# Netzteil_Darlington_v2_Frontpanel.net
KiCad netlist of a schematic drawn in EAGLE
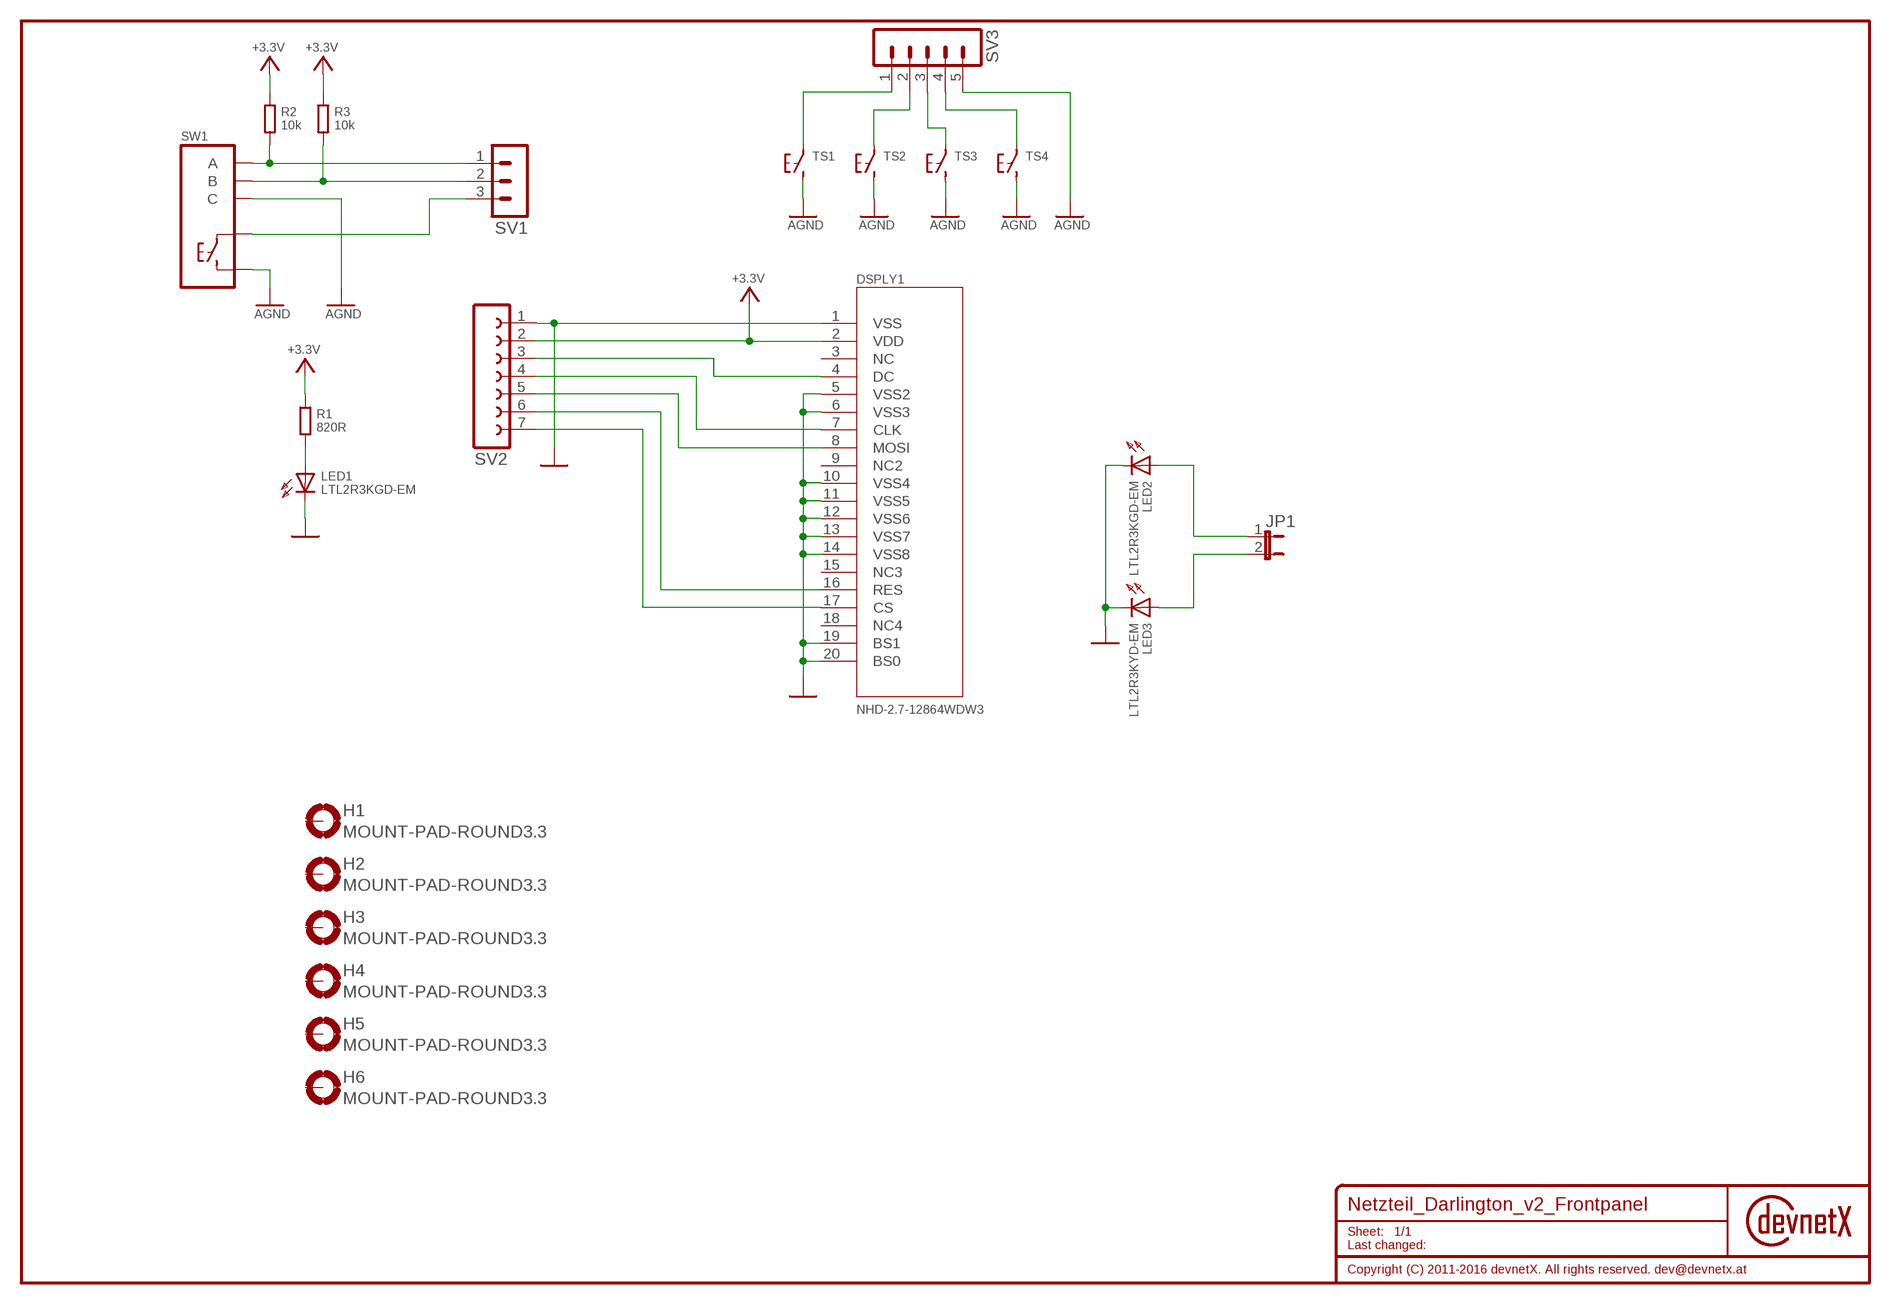
[diagram p0: schematic, sheet 1]

(export (version "E")
  (design (tool "Eeschema 10.0.6"))
  (components
    (comp (ref "DNX-NAME-1")
      (value "DOC-R1.27")
      (footprint "eagle-import:DRAWINGNAME-1.27")
      (libsource (lib "eagle-import") (part "DOC-R1.27"))
    )
    (comp (ref "DSPLY1")
      (value "NHD-2.7-12864WDW3")
      (footprint "eagle-import:NHD-2.7-12864WDW3")
      (libsource (lib "eagle-import") (part "NHD-2.7-12864WDW3"))
    )
    (comp (ref "H1")
      (value "MOUNT-PAD-ROUND3.3")
      (footprint "eagle-import:3,3-PAD")
      (libsource (lib "eagle-import") (part "MOUNT-PAD-ROUND3.3"))
    )
    (comp (ref "H2")
      (value "MOUNT-PAD-ROUND3.3")
      (footprint "eagle-import:3,3-PAD")
      (libsource (lib "eagle-import") (part "MOUNT-PAD-ROUND3.3"))
    )
    (comp (ref "H3")
      (value "MOUNT-PAD-ROUND3.3")
      (footprint "eagle-import:3,3-PAD")
      (libsource (lib "eagle-import") (part "MOUNT-PAD-ROUND3.3"))
    )
    (comp (ref "H4")
      (value "MOUNT-PAD-ROUND3.3")
      (footprint "eagle-import:3,3-PAD")
      (libsource (lib "eagle-import") (part "MOUNT-PAD-ROUND3.3"))
    )
    (comp (ref "H5")
      (value "MOUNT-PAD-ROUND3.3")
      (footprint "eagle-import:3,3-PAD")
      (libsource (lib "eagle-import") (part "MOUNT-PAD-ROUND3.3"))
    )
    (comp (ref "H6")
      (value "MOUNT-PAD-ROUND3.3")
      (footprint "eagle-import:3,3-PAD")
      (libsource (lib "eagle-import") (part "MOUNT-PAD-ROUND3.3"))
    )
    (comp (ref "JP1")
      (value "JP1E")
      (footprint "eagle-import:JP1")
      (libsource (lib "eagle-import") (part "JP1E"))
    )
    (comp (ref "LED1")
      (value "LTL2R3KGD-EM")
      (footprint "eagle-import:LED5MM")
      (libsource (lib "eagle-import") (part "LEDLED5MM"))
    )
    (comp (ref "LED2")
      (value "LTL2R3KGD-EM")
      (footprint "eagle-import:LED5MM")
      (libsource (lib "eagle-import") (part "LEDLED5MM"))
    )
    (comp (ref "LED3")
      (value "LTL2R3KYD-EM")
      (footprint "eagle-import:LED5MM")
      (libsource (lib "eagle-import") (part "LEDLED5MM"))
    )
    (comp (ref "R1")
      (value "820R")
      (footprint "eagle-import:C0805K")
      (libsource (lib "eagle-import") (part "R-SMD0805"))
    )
    (comp (ref "R2")
      (value "10k")
      (footprint "eagle-import:C0805K")
      (libsource (lib "eagle-import") (part "R-SMD0805"))
    )
    (comp (ref "R3")
      (value "10k")
      (footprint "eagle-import:C0805K")
      (libsource (lib "eagle-import") (part "R-SMD0805"))
    )
    (comp (ref "SV1")
      (value "MA03-1")
      (footprint "eagle-import:MA03-1")
      (libsource (lib "eagle-import") (part "MA03-1"))
    )
    (comp (ref "SV2")
      (value "FE07-1")
      (footprint "eagle-import:FE07")
      (libsource (lib "eagle-import") (part "FE07-1"))
    )
    (comp (ref "SV3")
      (value "MA05-1")
      (footprint "eagle-import:MA05-1")
      (libsource (lib "eagle-import") (part "MA05-1"))
    )
    (comp (ref "SW1")
      (value "EC12E-SW")
      (footprint "eagle-import:EC12E-SW")
      (libsource (lib "eagle-import") (part "EC12E-SW"))
    )
    (comp (ref "TS1")
      (value "TS1B3F-10XX")
      (footprint "eagle-import:B3F-10XX")
      (libsource (lib "eagle-import") (part "TS1B3F-10XX"))
    )
    (comp (ref "TS2")
      (value "TS1B3F-10XX")
      (footprint "eagle-import:B3F-10XX")
      (libsource (lib "eagle-import") (part "TS1B3F-10XX"))
    )
    (comp (ref "TS3")
      (value "TS1B3F-10XX")
      (footprint "eagle-import:B3F-10XX")
      (libsource (lib "eagle-import") (part "TS1B3F-10XX"))
    )
    (comp (ref "TS4")
      (value "TS1B3F-10XX")
      (footprint "eagle-import:B3F-10XX")
      (libsource (lib "eagle-import") (part "TS1B3F-10XX"))
    )
  )
  (nets
    (net (code "1") (name "+3.3V") (class "Default")
      (node (ref "DSPLY1") (pin "2") (pinfunction "VDD_2") (pintype "power_in"))
      (node (ref "R1") (pin "1") (pinfunction "1_1") (pintype "passive"))
      (node (ref "R2") (pin "1") (pinfunction "1_1") (pintype "passive"))
      (node (ref "R3") (pin "1") (pinfunction "1_1") (pintype "passive"))
      (node (ref "SV2") (pin "2") (pinfunction "2_2") (pintype "passive"))
    )
    (net (code "2") (name "AGND") (class "Default")
      (node (ref "SV3") (pin "5") (pinfunction "5_5") (pintype "passive"))
      (node (ref "SW1") (pin "2") (pinfunction "2_2") (pintype "passive"))
      (node (ref "SW1") (pin "C") (pinfunction "C_C") (pintype "passive"))
      (node (ref "TS1") (pin "3") (pinfunction "2_3") (pintype "passive"))
      (node (ref "TS2") (pin "3") (pinfunction "2_3") (pintype "passive"))
      (node (ref "TS3") (pin "3") (pinfunction "2_3") (pintype "passive"))
      (node (ref "TS4") (pin "3") (pinfunction "2_3") (pintype "passive"))
    )
    (net (code "3") (name "Net-(DSPLY1-CLK)") (class "Default")
      (node (ref "DSPLY1") (pin "7") (pinfunction "CLK_7") (pintype "bidirectional"))
      (node (ref "SV2") (pin "4") (pinfunction "4_4") (pintype "passive"))
    )
    (net (code "4") (name "Net-(DSPLY1-CS)") (class "Default")
      (node (ref "DSPLY1") (pin "17") (pinfunction "CS_17") (pintype "bidirectional"))
      (node (ref "SV2") (pin "7") (pinfunction "7_7") (pintype "passive"))
    )
    (net (code "5") (name "Net-(DSPLY1-DC)") (class "Default")
      (node (ref "DSPLY1") (pin "4") (pinfunction "DC_4") (pintype "bidirectional"))
      (node (ref "SV2") (pin "3") (pinfunction "3_3") (pintype "passive"))
    )
    (net (code "6") (name "Net-(DSPLY1-MOSI)") (class "Default")
      (node (ref "DSPLY1") (pin "8") (pinfunction "MOSI_8") (pintype "bidirectional"))
      (node (ref "SV2") (pin "5") (pinfunction "5_5") (pintype "passive"))
    )
    (net (code "7") (name "Net-(DSPLY1-RES)") (class "Default")
      (node (ref "DSPLY1") (pin "16") (pinfunction "RES_16") (pintype "bidirectional"))
      (node (ref "SV2") (pin "6") (pinfunction "6_6") (pintype "passive"))
    )
    (net (code "8") (name "Net-(JP1-Pad1)") (class "Default")
      (node (ref "JP1") (pin "1") (pinfunction "1_1") (pintype "passive"))
      (node (ref "LED2") (pin "A") (pinfunction "A_A") (pintype "passive"))
    )
    (net (code "9") (name "Net-(JP1-Pad2)") (class "Default")
      (node (ref "JP1") (pin "2") (pinfunction "2_2") (pintype "passive"))
      (node (ref "LED3") (pin "A") (pinfunction "A_A") (pintype "passive"))
    )
    (net (code "10") (name "Net-(LED1-PadA)") (class "Default")
      (node (ref "LED1") (pin "A") (pinfunction "A_A") (pintype "passive"))
      (node (ref "R1") (pin "2") (pinfunction "2_2") (pintype "passive"))
    )
    (net (code "11") (name "Net-(R2-Pad2)") (class "Default")
      (node (ref "R2") (pin "2") (pinfunction "2_2") (pintype "passive"))
      (node (ref "SV1") (pin "1") (pinfunction "1_1") (pintype "passive"))
      (node (ref "SW1") (pin "A") (pinfunction "A_A") (pintype "passive"))
    )
    (net (code "12") (name "Net-(R3-Pad2)") (class "Default")
      (node (ref "R3") (pin "2") (pinfunction "2_2") (pintype "passive"))
      (node (ref "SV1") (pin "2") (pinfunction "2_2") (pintype "passive"))
      (node (ref "SW1") (pin "B") (pinfunction "B_B") (pintype "passive"))
    )
    (net (code "13") (name "Net-(SV1-Pad3)") (class "Default")
      (node (ref "SV1") (pin "3") (pinfunction "3_3") (pintype "passive"))
      (node (ref "SW1") (pin "1") (pinfunction "1_1") (pintype "passive"))
    )
    (net (code "14") (name "Net-(SV3-Pad1)") (class "Default")
      (node (ref "SV3") (pin "1") (pinfunction "1_1") (pintype "passive"))
      (node (ref "TS1") (pin "1") (pinfunction "1_1") (pintype "passive"))
    )
    (net (code "15") (name "Net-(SV3-Pad2)") (class "Default")
      (node (ref "SV3") (pin "2") (pinfunction "2_2") (pintype "passive"))
      (node (ref "TS2") (pin "1") (pinfunction "1_1") (pintype "passive"))
    )
    (net (code "16") (name "Net-(SV3-Pad3)") (class "Default")
      (node (ref "SV3") (pin "3") (pinfunction "3_3") (pintype "passive"))
      (node (ref "TS3") (pin "1") (pinfunction "1_1") (pintype "passive"))
    )
    (net (code "17") (name "Net-(SV3-Pad4)") (class "Default")
      (node (ref "SV3") (pin "4") (pinfunction "4_4") (pintype "passive"))
      (node (ref "TS4") (pin "1") (pinfunction "1_1") (pintype "passive"))
    )
    (net (code "18") (name "VSS") (class "Default")
      (node (ref "DSPLY1") (pin "1") (pinfunction "VSS_1") (pintype "power_in"))
      (node (ref "DSPLY1") (pin "10") (pinfunction "VSS4_10") (pintype "power_in"))
      (node (ref "DSPLY1") (pin "11") (pinfunction "VSS5_11") (pintype "power_in"))
      (node (ref "DSPLY1") (pin "12") (pinfunction "VSS6_12") (pintype "power_in"))
      (node (ref "DSPLY1") (pin "13") (pinfunction "VSS7_13") (pintype "power_in"))
      (node (ref "DSPLY1") (pin "14") (pinfunction "VSS8_14") (pintype "power_in"))
      (node (ref "DSPLY1") (pin "19") (pinfunction "BS1_19") (pintype "bidirectional"))
      (node (ref "DSPLY1") (pin "20") (pinfunction "BS0_20") (pintype "bidirectional"))
      (node (ref "DSPLY1") (pin "5") (pinfunction "VSS2_5") (pintype "power_in"))
      (node (ref "DSPLY1") (pin "6") (pinfunction "VSS3_6") (pintype "power_in"))
      (node (ref "LED1") (pin "C") (pinfunction "C_C") (pintype "passive"))
      (node (ref "LED2") (pin "C") (pinfunction "C_C") (pintype "passive"))
      (node (ref "LED3") (pin "C") (pinfunction "C_C") (pintype "passive"))
      (node (ref "SV2") (pin "1") (pinfunction "1_1") (pintype "passive"))
    )
    (net (code "19") (name "unconnected-(DSPLY1-NC-Pad3)") (class "Default")
      (node (ref "DSPLY1") (pin "3") (pinfunction "NC_3") (pintype "no_connect"))
    )
    (net (code "20") (name "unconnected-(DSPLY1-NC2-Pad9)") (class "Default")
      (node (ref "DSPLY1") (pin "9") (pinfunction "NC2_9") (pintype "no_connect"))
    )
    (net (code "21") (name "unconnected-(DSPLY1-NC3-Pad15)") (class "Default")
      (node (ref "DSPLY1") (pin "15") (pinfunction "NC3_15") (pintype "no_connect"))
    )
    (net (code "22") (name "unconnected-(DSPLY1-NC4-Pad18)") (class "Default")
      (node (ref "DSPLY1") (pin "18") (pinfunction "NC4_18") (pintype "no_connect"))
    )
    (net (code "23") (name "unconnected-(H1-MOUNT-PadB3,3)") (class "Default")
      (node (ref "H1") (pin "B3,3") (pinfunction "MOUNT_B3,3") (pintype "passive"))
    )
    (net (code "24") (name "unconnected-(H2-MOUNT-PadB3,3)") (class "Default")
      (node (ref "H2") (pin "B3,3") (pinfunction "MOUNT_B3,3") (pintype "passive"))
    )
    (net (code "25") (name "unconnected-(H3-MOUNT-PadB3,3)") (class "Default")
      (node (ref "H3") (pin "B3,3") (pinfunction "MOUNT_B3,3") (pintype "passive"))
    )
    (net (code "26") (name "unconnected-(H4-MOUNT-PadB3,3)") (class "Default")
      (node (ref "H4") (pin "B3,3") (pinfunction "MOUNT_B3,3") (pintype "passive"))
    )
    (net (code "27") (name "unconnected-(H5-MOUNT-PadB3,3)") (class "Default")
      (node (ref "H5") (pin "B3,3") (pinfunction "MOUNT_B3,3") (pintype "passive"))
    )
    (net (code "28") (name "unconnected-(H6-MOUNT-PadB3,3)") (class "Default")
      (node (ref "H6") (pin "B3,3") (pinfunction "MOUNT_B3,3") (pintype "passive"))
    )
  )
)
